# rx_path.net
KiCad netlist of a schematic drawn in Altium Designer
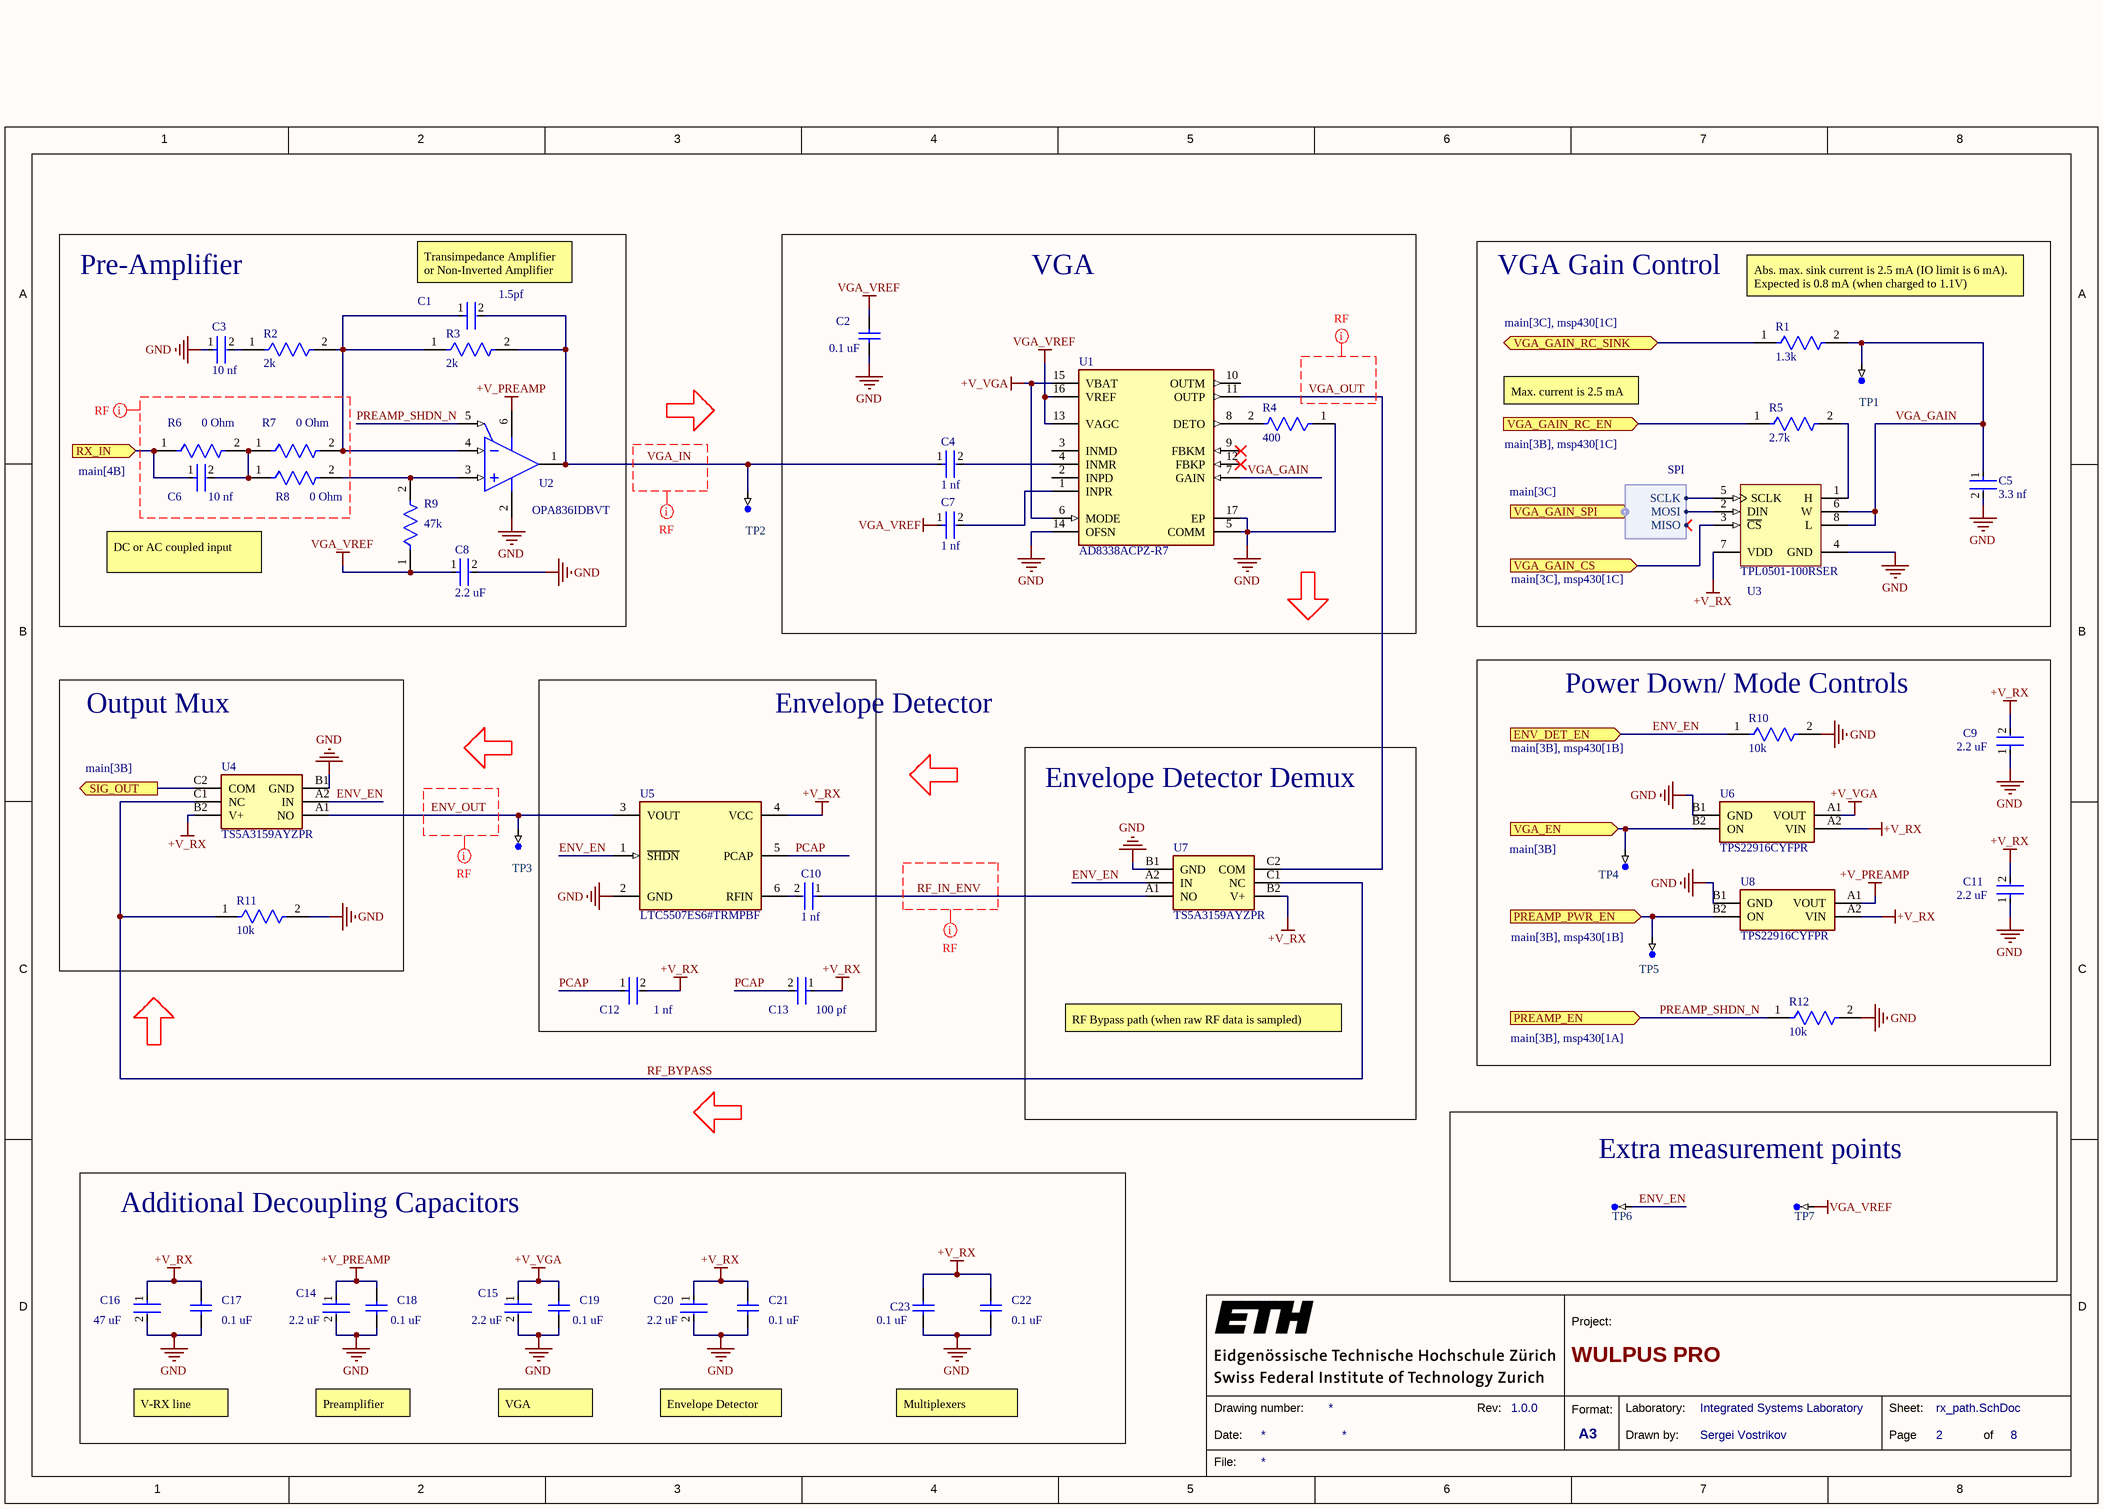
[diagram p0: rx_path.SchDoc]

(export (version "E")
  (design (tool "Eeschema 10.0.6"))
  (components
    (comp (ref "C1")
      (value "1.5pf")
      (footprint "FP-GJM155-0_05-IPC_C")
      (description "GJM1555C1H1R5BB01D")
      (fields (field (name "VOLTAGE") "50V"))
      (libsource (lib "Altium Content Vault") (part "02cd4be3c70576c341d710602a673aa"))
    )
    (comp (ref "C2")
      (value "0.1 uF")
      (footprint "CAPC1005X55X30LL05T10")
      (description "C0402C104K4RACTU")
      (fields (field (name "MANUFACTURER") "Kemet"))
      (libsource (lib "Altium Content Vault") (part "CAP"))
    )
    (comp (ref "C3")
      (value "10 nf")
      (footprint "FP-GRM033-0_03-IPC_B")
      (description "GRM033R71A103KA01D")
      (fields (field (name "VOLTAGE") "10V") (field (name "TOLERANCE") "10%"))
      (libsource (lib "Altium Content Vault") (part "b4654b650e69147ec39a6b967a45e02"))
    )
    (comp (ref "C4")
      (value "1 nf")
      (footprint "FP-GRM155-0_05-IPC_B")
      (description "GRM1555C1H102JA01D")
      (fields (field (name "TOLERANCE") "5%") (field (name "VOLTAGE") "50V"))
      (libsource (lib "Altium Content Vault") (part "02cd4be3c70576c341d710602a673aa"))
    )
    (comp (ref "C5")
      (value "3.3 nf")
      (footprint "FP-0402-L_1_0_1-W_0_5_0_1-IPC_C")
      (description "04025C332JAT2A")
      (fields (field (name "TOLERANCE") "5%"))
      (libsource (lib "Altium Content Vault") (part "b4654b650e69147ec39a6b967a45e02"))
    )
    (comp (ref "C6")
      (value "10 nf")
      (footprint "FP-GRM033-0_03-IPC_B")
      (description "GRM033R71A103KA01D")
      (fields (field (name "VOLTAGE") "10V") (field (name "TOLERANCE") "10%"))
      (libsource (lib "Altium Content Vault") (part "b4654b650e69147ec39a6b967a45e02"))
    )
    (comp (ref "C7")
      (value "1 nf")
      (footprint "FP-GRM155-0_05-IPC_B")
      (description "GRM1555C1H102JA01D")
      (fields (field (name "TOLERANCE") "5%") (field (name "VOLTAGE") "50V"))
      (libsource (lib "Altium Content Vault") (part "02cd4be3c70576c341d710602a673aa"))
    )
    (comp (ref "C8")
      (value "2.2 uF")
      (footprint "FP-C1005-050-0_15-0_1-MFG")
      (description "C1005X7S1A225K050BC")
      (fields (field (name "TOLERANCE") "10%"))
      (libsource (lib "Altium Content Vault") (part "b4654b650e69147ec39a6b967a45e02"))
    )
    (comp (ref "C9")
      (value "2.2 uF")
      (footprint "FP-C1005-050-0_15-0_1-MFG")
      (description "C1005X7S1A225K050BC")
      (fields (field (name "TOLERANCE") "10%"))
      (libsource (lib "Altium Content Vault") (part "b4654b650e69147ec39a6b967a45e02"))
    )
    (comp (ref "C10")
      (value "1 nf")
      (footprint "FP-GRM155-0_05-IPC_B")
      (description "GRM1555C1H102JA01D")
      (fields (field (name "TOLERANCE") "5%") (field (name "VOLTAGE") "50V"))
      (libsource (lib "Altium Content Vault") (part "02cd4be3c70576c341d710602a673aa"))
    )
    (comp (ref "C11")
      (value "2.2 uF")
      (footprint "FP-C1005-050-0_15-0_1-MFG")
      (description "C1005X7S1A225K050BC")
      (fields (field (name "TOLERANCE") "10%"))
      (libsource (lib "Altium Content Vault") (part "b4654b650e69147ec39a6b967a45e02"))
    )
    (comp (ref "C12")
      (value "1 nf")
      (footprint "FP-GRM155-0_05-IPC_B")
      (description "GRM1555C1H102JA01D")
      (fields (field (name "TOLERANCE") "5%") (field (name "VOLTAGE") "50V"))
      (libsource (lib "Altium Content Vault") (part "02cd4be3c70576c341d710602a673aa"))
    )
    (comp (ref "C13")
      (value "100 pf")
      (footprint "FP-0402-L_1_0_1-W_0_5_0_1-MFG")
      (description "04025A101FAT2A")
      (fields (field (name "VOLTAGE") "50V") (field (name "TOLERANCE") "1%"))
      (libsource (lib "Altium Content Vault") (part "b4654b650e69147ec39a6b967a45e02"))
    )
    (comp (ref "C14")
      (value "2.2 uF")
      (footprint "FP-C1005-050-0_15-0_1-MFG")
      (description "C1005X7S1A225K050BC")
      (fields (field (name "TOLERANCE") "10%"))
      (libsource (lib "Altium Content Vault") (part "b4654b650e69147ec39a6b967a45e02"))
    )
    (comp (ref "C15")
      (value "2.2 uF")
      (footprint "FP-C1005-050-0_15-0_1-MFG")
      (description "C1005X7S1A225K050BC")
      (fields (field (name "TOLERANCE") "10%"))
      (libsource (lib "Altium Content Vault") (part "b4654b650e69147ec39a6b967a45e02"))
    )
    (comp (ref "C16")
      (value "47 uF")
      (footprint "FP-GRM188-0_2-MFG")
      (description "GRM188R60J476ME01D")
      (fields (field (name "TOLERANCE") "20%"))
      (libsource (lib "Altium Content Vault") (part "b4654b650e69147ec39a6b967a45e02"))
    )
    (comp (ref "C17")
      (value "0.1 uF")
      (footprint "CAPC1005X55X30LL05T10")
      (description "C0402C104K4RACTU")
      (fields (field (name "MANUFACTURER") "Kemet"))
      (libsource (lib "Altium Content Vault") (part "CAP"))
    )
    (comp (ref "C18")
      (value "0.1 uF")
      (footprint "CAPC1005X55X30LL05T10")
      (description "C0402C104K4RACTU")
      (fields (field (name "MANUFACTURER") "Kemet"))
      (libsource (lib "Altium Content Vault") (part "CAP"))
    )
    (comp (ref "C19")
      (value "0.1 uF")
      (footprint "CAPC1005X55X30LL05T10")
      (description "C0402C104K4RACTU")
      (fields (field (name "MANUFACTURER") "Kemet"))
      (libsource (lib "Altium Content Vault") (part "CAP"))
    )
    (comp (ref "C20")
      (value "2.2 uF")
      (footprint "FP-C1005-050-0_15-0_1-MFG")
      (description "C1005X7S1A225K050BC")
      (fields (field (name "TOLERANCE") "10%"))
      (libsource (lib "Altium Content Vault") (part "b4654b650e69147ec39a6b967a45e02"))
    )
    (comp (ref "C21")
      (value "0.1 uF")
      (footprint "CAPC1005X55X30LL05T10")
      (description "C0402C104K4RACTU")
      (fields (field (name "MANUFACTURER") "Kemet"))
      (libsource (lib "Altium Content Vault") (part "CAP"))
    )
    (comp (ref "C22")
      (value "0.1 uF")
      (footprint "CAPC1005X55X30LL05T10")
      (description "C0402C104K4RACTU")
      (fields (field (name "MANUFACTURER") "Kemet"))
      (libsource (lib "Altium Content Vault") (part "CAP"))
    )
    (comp (ref "C23")
      (value "0.1 uF")
      (footprint "CAPC1005X55X30LL05T10")
      (description "C0402C104K4RACTU")
      (fields (field (name "MANUFACTURER") "Kemet"))
      (libsource (lib "Altium Content Vault") (part "CAP"))
    )
    (comp (ref "R1")
      (value "1.3k")
      (footprint "FP-CRCW0402-e3-IPC_B")
      (description "CRCW04021K30JNED")
      (fields (field (name "TOLERANCE") "5%"))
      (libsource (lib "Altium Content Vault") (part "1029c3af85768c4190bb7ad29bc67b5"))
    )
    (comp (ref "R2")
      (value "2k")
      (footprint "FP-ERJ2RK-MFG")
      (description "ERJ-2RKF2001X")
      (fields (field (name "TOLERANCE") "1%"))
      (libsource (lib "Altium Content Vault") (part "1029c3af85768c4190bb7ad29bc67b5"))
    )
    (comp (ref "R3")
      (value "2k")
      (footprint "FP-ERJ2RK-MFG")
      (description "ERJ-2RKF2001X")
      (fields (field (name "TOLERANCE") "1%"))
      (libsource (lib "Altium Content Vault") (part "1029c3af85768c4190bb7ad29bc67b5"))
    )
    (comp (ref "R4")
      (value "400")
      (footprint "FP-CRCW0402-C-e3-MFG")
      (description "CRCW04021R00FKEDC")
      (fields (field (name "TOLERANCE") "1%"))
      (libsource (lib "Altium Content Vault") (part "1029c3af85768c4190bb7ad29bc67b5"))
    )
    (comp (ref "R5")
      (value "2.7k")
      (footprint "FP-MCS0402-IPC_B")
      (description "MCS04020C2701FE000")
      (fields (field (name "TOLERANCE") "1%"))
      (libsource (lib "Altium Content Vault") (part "1029c3af85768c4190bb7ad29bc67b5"))
    )
    (comp (ref "R6")
      (value "0 Ohm")
      (footprint "FP-CRCW0402-e3-IPC_C")
      (description "CRCW04020000Z0ED")
      (fields (field (name "TOLERANCE") "5%"))
      (libsource (lib "Altium Content Vault") (part "1029c3af85768c4190bb7ad29bc67b5"))
    )
    (comp (ref "R7")
      (value "0 Ohm")
      (footprint "FP-CRCW0402-e3-IPC_C")
      (description "CRCW04020000Z0ED")
      (fields (field (name "TOLERANCE") "5%"))
      (libsource (lib "Altium Content Vault") (part "1029c3af85768c4190bb7ad29bc67b5"))
    )
    (comp (ref "R8")
      (value "0 Ohm")
      (footprint "FP-CRCW0402-e3-IPC_C")
      (description "CRCW04020000Z0ED")
      (fields (field (name "TOLERANCE") "5%"))
      (libsource (lib "Altium Content Vault") (part "1029c3af85768c4190bb7ad29bc67b5"))
    )
    (comp (ref "R9")
      (value "47k")
      (footprint "FP-RMCF0201-MFG")
      (description "RMCF0201JT47K0")
      (fields (field (name "TOLERANCE") "5%"))
      (libsource (lib "Altium Content Vault") (part "1029c3af85768c4190bb7ad29bc67b5"))
    )
    (comp (ref "R10")
      (value "10k")
      (footprint "FP-CRCW0402-e3-IPC_B")
      (description "CRCW040210K0JNED")
      (fields (field (name "TOLERANCE") "5%"))
      (libsource (lib "Altium Content Vault") (part "1029c3af85768c4190bb7ad29bc67b5"))
    )
    (comp (ref "R11")
      (value "10k")
      (footprint "FP-CRCW0402-e3-IPC_B")
      (description "CRCW040210K0JNED")
      (fields (field (name "TOLERANCE") "5%"))
      (libsource (lib "Altium Content Vault") (part "1029c3af85768c4190bb7ad29bc67b5"))
    )
    (comp (ref "R12")
      (value "10k")
      (footprint "FP-CRCW0402-e3-IPC_B")
      (description "CRCW040210K0JNED")
      (fields (field (name "TOLERANCE") "5%"))
      (libsource (lib "Altium Content Vault") (part "1029c3af85768c4190bb7ad29bc67b5"))
    )
    (comp (ref "TP1")
      (value "TP-SM-C-100")
      (footprint "TP-SM-C-100")
      (description "Test Point, Surface Mount, Circular, Pad Diameter 1 mm")
      (libsource (lib "wulpus") (part "CMP-0484-00002-1"))
    )
    (comp (ref "TP2")
      (value "TP-SM-C-100")
      (footprint "TP-SM-C-100")
      (description "Test Point, Surface Mount, Circular, Pad Diameter 1 mm")
      (libsource (lib "wulpus") (part "CMP-0484-00002-1"))
    )
    (comp (ref "TP3")
      (value "TP-SM-C-100")
      (footprint "TP-SM-C-100")
      (description "Test Point, Surface Mount, Circular, Pad Diameter 1 mm")
      (libsource (lib "wulpus") (part "CMP-0484-00002-1"))
    )
    (comp (ref "TP4")
      (value "TP-SM-C-100")
      (footprint "TP-SM-C-100")
      (description "Test Point, Surface Mount, Circular, Pad Diameter 1 mm")
      (libsource (lib "wulpus") (part "CMP-0484-00002-1"))
    )
    (comp (ref "TP5")
      (value "TP-SM-C-100")
      (footprint "TP-SM-C-100")
      (description "Test Point, Surface Mount, Circular, Pad Diameter 1 mm")
      (libsource (lib "wulpus") (part "CMP-0484-00002-1"))
    )
    (comp (ref "TP6")
      (value "TP-SM-C-100")
      (footprint "TP-SM-C-100")
      (description "Test Point, Surface Mount, Circular, Pad Diameter 1 mm")
      (libsource (lib "wulpus") (part "CMP-0484-00002-1"))
    )
    (comp (ref "TP7")
      (value "TP-SM-C-100")
      (footprint "TP-SM-C-100")
      (description "Test Point, Surface Mount, Circular, Pad Diameter 1 mm")
      (libsource (lib "wulpus") (part "CMP-0484-00002-1"))
    )
    (comp (ref "U1")
      (value "AD8338ACPZ-R7")
      (footprint "FP-CP-16-22-IPC_C")
      (description "IC OPAMP VGA 1 CIRCUIT 16LFCSP")
      (fields
        (field (name "OCTOPART") "https://octopart.com/ad8338acpz-r7-analog+devices-21054770")
        (field (name "MANUFACTURER") "Analog Devices")
      )
      (libsource (lib "Altium Content Vault") (part "4ce7887af0b7713ffabab50ab6d8fb3"))
    )
    (comp (ref "U2")
      (value "OPA836IDBVT")
      (footprint "DBV0006A_L")
      (fields (field (name "MANUFACTURER") "Texas Instruments"))
      (libsource (lib "wulpus") (part "CMP-0018-00480-2"))
    )
    (comp (ref "U3")
      (value "TPL0501-100RSER")
      (footprint "TI-RSE8_V")
      (fields (field (name "MANUFACTURER") "Texas Instruments"))
      (libsource (lib "Altium Content Vault") (part "TI-TPL0501-100RSE8"))
    )
    (comp (ref "U4")
      (value "TS5A3159AYZPR")
      (footprint "BGA6C50P2X3_89X139X50")
      (description "Analogue Switch ICs SPDT ANALOG SWITCH")
      (libsource (lib "") (part "TS5A3159AYZPR_1"))
    )
    (comp (ref "U5")
      (value "LTC5507ES6#TRMPBF")
      (footprint "FP-LTC5507ES6#TRMPBF-IPC_B")
      (description "IC RF DETECT 100KHZ-1GHZ TSOT23")
      (fields
        (field (name "OCTOPART") "https://octopart.com/ltc5507es6%23trmpbf-analog+devices-88320008")
        (field (name "MANUFACTURER") "Analog Devices")
      )
      (libsource (lib "Altium Content Vault") (part "942e158bd38935f4e9b1d9ad82e87f8"))
    )
    (comp (ref "U6")
      (value "TPS22916CYFPR")
      (footprint "BGA4C40P2X2_78X78X50")
      (description "TPS22916 5.5-V, 2-A Ultra-Low Leakage Load Switch")
      (libsource (lib "TPS22916CYFPR") (part "TPS22916CYFPR"))
    )
    (comp (ref "U7")
      (value "TS5A3159AYZPR")
      (footprint "BGA6C50P2X3_89X139X50")
      (description "Analogue Switch ICs SPDT ANALOG SWITCH")
      (libsource (lib "TS5A3159AYZPR") (part "TS5A3159AYZPR"))
    )
    (comp (ref "U8")
      (value "TPS22916CYFPR")
      (footprint "BGA4C40P2X2_78X78X50")
      (description "TPS22916 5.5-V, 2-A Ultra-Low Leakage Load Switch")
      (libsource (lib "TPS22916CYFPR") (part "TPS22916CYFPR"))
    )
  )
  (nets
    (net (code "2") (name "+V_PREAMP") (class "Default")
      (node (ref "C14") (pin "1") (pinfunction "1_1") (pintype "passive"))
      (node (ref "C18") (pin "2") (pinfunction "2_2") (pintype "passive"))
      (node (ref "U2") (pin "6") (pinfunction "VS+_6") (pintype "power_in"))
      (node (ref "U8") (pin "A1") (pinfunction "VOUT_A1") (pintype "passive"))
    )
    (net (code "3") (name "+V_RX") (class "Default")
      (node (ref "C11") (pin "2") (pinfunction "2_2") (pintype "passive"))
      (node (ref "C12") (pin "2") (pinfunction "2_2") (pintype "passive"))
      (node (ref "C13") (pin "1") (pinfunction "1_1") (pintype "passive"))
      (node (ref "C16") (pin "1") (pinfunction "1_1") (pintype "passive"))
      (node (ref "C17") (pin "2") (pinfunction "2_2") (pintype "passive"))
      (node (ref "C20") (pin "1") (pinfunction "1_1") (pintype "passive"))
      (node (ref "C21") (pin "2") (pinfunction "2_2") (pintype "passive"))
      (node (ref "C22") (pin "2") (pinfunction "2_2") (pintype "passive"))
      (node (ref "C23") (pin "2") (pinfunction "2_2") (pintype "passive"))
      (node (ref "C9") (pin "2") (pinfunction "2_2") (pintype "passive"))
      (node (ref "U3") (pin "7") (pinfunction "VDD_7") (pintype "power_in"))
      (node (ref "U4") (pin "B2") (pinfunction "V+_B2") (pintype "passive"))
      (node (ref "U5") (pin "4") (pinfunction "VCC_4") (pintype "power_in"))
      (node (ref "U6") (pin "A2") (pinfunction "VIN_A2") (pintype "passive"))
      (node (ref "U7") (pin "B2") (pinfunction "V+_B2") (pintype "passive"))
      (node (ref "U8") (pin "A2") (pinfunction "VIN_A2") (pintype "passive"))
    )
    (net (code "4") (name "+V_VGA") (class "Default")
      (node (ref "C15") (pin "1") (pinfunction "1_1") (pintype "passive"))
      (node (ref "C19") (pin "2") (pinfunction "2_2") (pintype "passive"))
      (node (ref "U1") (pin "15") (pinfunction "VBAT_15") (pintype "power_in"))
      (node (ref "U1") (pin "6") (pinfunction "MODE_6") (pintype "input"))
      (node (ref "U6") (pin "A1") (pinfunction "VOUT_A1") (pintype "passive"))
    )
    (net (code "5") (name "/ENV_EN") (class "Default")
      (node (ref "R10") (pin "1") (pinfunction "1_1") (pintype "passive"))
      (node (ref "TP6") (pin "1") (pinfunction "1_1") (pintype "input"))
      (node (ref "U4") (pin "A2") (pinfunction "IN_A2") (pintype "passive"))
      (node (ref "U5") (pin "1") (pinfunction "~{SHDN}_1") (pintype "input"))
      (node (ref "U7") (pin "A2") (pinfunction "IN_A2") (pintype "passive"))
    )
    (net (code "6") (name "/ENV_OUT") (class "Default")
      (node (ref "TP3") (pin "1") (pinfunction "1_1") (pintype "input"))
      (node (ref "U4") (pin "A1") (pinfunction "NO_A1") (pintype "passive"))
      (node (ref "U5") (pin "3") (pinfunction "VOUT_3") (pintype "passive"))
    )
    (net (code "7") (name "/MOSI") (class "Default")
      (node (ref "U3") (pin "2") (pinfunction "DIN_2") (pintype "input"))
    )
    (net (code "8") (name "/PCAP") (class "Default")
      (node (ref "C12") (pin "1") (pinfunction "1_1") (pintype "passive"))
      (node (ref "C13") (pin "2") (pinfunction "2_2") (pintype "passive"))
      (node (ref "U5") (pin "5") (pinfunction "PCAP_5") (pintype "passive"))
    )
    (net (code "9") (name "/PREAMP_PWR_EN") (class "Default")
      (node (ref "TP5") (pin "1") (pinfunction "1_1") (pintype "input"))
      (node (ref "U8") (pin "B2") (pinfunction "ON_B2") (pintype "passive"))
    )
    (net (code "10") (name "/PREAMP_SHDN_N") (class "Default")
      (node (ref "R12") (pin "1") (pinfunction "1_1") (pintype "passive"))
      (node (ref "U2") (pin "5") (pinfunction "~{PD}_5") (pintype "input"))
    )
    (net (code "11") (name "/RF_BYPASS") (class "Default")
      (node (ref "R11") (pin "1") (pinfunction "1_1") (pintype "passive"))
      (node (ref "U4") (pin "C1") (pinfunction "NC_C1") (pintype "passive"))
      (node (ref "U7") (pin "C1") (pinfunction "NC_C1") (pintype "passive"))
    )
    (net (code "12") (name "/RF_IN_ENV") (class "Default")
      (node (ref "C10") (pin "1") (pinfunction "1_1") (pintype "passive"))
      (node (ref "U7") (pin "A1") (pinfunction "NO_A1") (pintype "passive"))
    )
    (net (code "13") (name "/RX_IN") (class "Default")
      (node (ref "C6") (pin "1") (pinfunction "1_1") (pintype "passive"))
      (node (ref "R6") (pin "1") (pinfunction "1_1") (pintype "passive"))
    )
    (net (code "14") (name "/SCLK") (class "Default")
      (node (ref "U3") (pin "5") (pinfunction "SCLK_5") (pintype "input"))
    )
    (net (code "15") (name "/SIG_OUT") (class "Default")
      (node (ref "U4") (pin "C2") (pinfunction "COM_C2") (pintype "passive"))
    )
    (net (code "16") (name "/VGA_EN") (class "Default")
      (node (ref "TP4") (pin "1") (pinfunction "1_1") (pintype "input"))
      (node (ref "U6") (pin "B2") (pinfunction "ON_B2") (pintype "passive"))
    )
    (net (code "17") (name "/VGA_GAIN") (class "Default")
      (node (ref "C5") (pin "1") (pinfunction "1_1") (pintype "passive"))
      (node (ref "R1") (pin "2") (pinfunction "2_2") (pintype "passive"))
      (node (ref "TP1") (pin "1") (pinfunction "1_1") (pintype "input"))
      (node (ref "U1") (pin "7") (pinfunction "GAIN_7") (pintype "input"))
      (node (ref "U3") (pin "6") (pinfunction "W_6") (pintype "passive"))
      (node (ref "U3") (pin "8") (pinfunction "L_8") (pintype "passive"))
    )
    (net (code "18") (name "/VGA_GAIN_CS") (class "Default")
      (node (ref "U3") (pin "3") (pinfunction "~{CS}_3") (pintype "input"))
    )
    (net (code "19") (name "/VGA_GAIN_RC_EN") (class "Default")
      (node (ref "R5") (pin "1") (pinfunction "1_1") (pintype "passive"))
    )
    (net (code "20") (name "/VGA_GAIN_RC_SINK") (class "Default")
      (node (ref "R1") (pin "1") (pinfunction "1_1") (pintype "passive"))
    )
    (net (code "21") (name "/VGA_IN") (class "Default")
      (node (ref "C1") (pin "2") (pinfunction "2_2") (pintype "passive"))
      (node (ref "C4") (pin "1") (pinfunction "1_1") (pintype "passive"))
      (node (ref "R3") (pin "2") (pinfunction "2_2") (pintype "passive"))
      (node (ref "TP2") (pin "1") (pinfunction "1_1") (pintype "input"))
      (node (ref "U2") (pin "1") (pinfunction "VOUT_1") (pintype "tri_state"))
    )
    (net (code "22") (name "/VGA_OUT") (class "Default")
      (node (ref "U1") (pin "11") (pinfunction "OUTP_11") (pintype "output"))
      (node (ref "U7") (pin "C2") (pinfunction "COM_C2") (pintype "passive"))
    )
    (net (code "24") (name "GND") (class "Default")
      (node (ref "C11") (pin "1") (pinfunction "1_1") (pintype "passive"))
      (node (ref "C14") (pin "2") (pinfunction "2_2") (pintype "passive"))
      (node (ref "C15") (pin "2") (pinfunction "2_2") (pintype "passive"))
      (node (ref "C16") (pin "2") (pinfunction "2_2") (pintype "passive"))
      (node (ref "C17") (pin "1") (pinfunction "1_1") (pintype "passive"))
      (node (ref "C18") (pin "1") (pinfunction "1_1") (pintype "passive"))
      (node (ref "C19") (pin "1") (pinfunction "1_1") (pintype "passive"))
      (node (ref "C2") (pin "1") (pinfunction "1_1") (pintype "passive"))
      (node (ref "C20") (pin "2") (pinfunction "2_2") (pintype "passive"))
      (node (ref "C21") (pin "1") (pinfunction "1_1") (pintype "passive"))
      (node (ref "C22") (pin "1") (pinfunction "1_1") (pintype "passive"))
      (node (ref "C23") (pin "1") (pinfunction "1_1") (pintype "passive"))
      (node (ref "C3") (pin "1") (pinfunction "1_1") (pintype "passive"))
      (node (ref "C5") (pin "2") (pinfunction "2_2") (pintype "passive"))
      (node (ref "C8") (pin "2") (pinfunction "2_2") (pintype "passive"))
      (node (ref "C9") (pin "1") (pinfunction "1_1") (pintype "passive"))
      (node (ref "R10") (pin "2") (pinfunction "2_2") (pintype "passive"))
      (node (ref "R11") (pin "2") (pinfunction "2_2") (pintype "passive"))
      (node (ref "R12") (pin "2") (pinfunction "2_2") (pintype "passive"))
      (node (ref "R4") (pin "1") (pinfunction "1_1") (pintype "passive"))
      (node (ref "U1") (pin "14") (pinfunction "OFSN_14") (pintype "passive"))
      (node (ref "U1") (pin "17") (pinfunction "EP_17") (pintype "power_in"))
      (node (ref "U1") (pin "5") (pinfunction "COMM_5") (pintype "power_in"))
      (node (ref "U2") (pin "2") (pinfunction "VS-_2") (pintype "power_in"))
      (node (ref "U3") (pin "4") (pinfunction "GND_4") (pintype "power_in"))
      (node (ref "U4") (pin "B1") (pinfunction "GND_B1") (pintype "passive"))
      (node (ref "U5") (pin "2") (pinfunction "GND_2") (pintype "power_in"))
      (node (ref "U6") (pin "B1") (pinfunction "GND_B1") (pintype "passive"))
      (node (ref "U7") (pin "B1") (pinfunction "GND_B1") (pintype "passive"))
      (node (ref "U8") (pin "B1") (pinfunction "GND_B1") (pintype "passive"))
    )
    (net (code "25") (name "Net-(C3-Pad2)") (class "Default")
      (node (ref "C3") (pin "2") (pinfunction "2_2") (pintype "passive"))
      (node (ref "R2") (pin "1") (pinfunction "1_1") (pintype "passive"))
    )
    (net (code "26") (name "Net-(C6-Pad2)") (class "Default")
      (node (ref "C6") (pin "2") (pinfunction "2_2") (pintype "passive"))
      (node (ref "R6") (pin "2") (pinfunction "2_2") (pintype "passive"))
      (node (ref "R7") (pin "1") (pinfunction "1_1") (pintype "passive"))
      (node (ref "R8") (pin "1") (pinfunction "1_1") (pintype "passive"))
    )
    (net (code "27") (name "Net-(U1-DETO)") (class "Default")
      (node (ref "R4") (pin "2") (pinfunction "2_2") (pintype "passive"))
      (node (ref "U1") (pin "8") (pinfunction "DETO_8") (pintype "output"))
    )
    (net (code "28") (name "Net-(U1-INMR)") (class "Default")
      (node (ref "C4") (pin "2") (pinfunction "2_2") (pintype "passive"))
      (node (ref "U1") (pin "4") (pinfunction "INMR_4") (pintype "passive"))
    )
    (net (code "29") (name "Net-(U1-INPR)") (class "Default")
      (node (ref "C7") (pin "2") (pinfunction "2_2") (pintype "passive"))
      (node (ref "U1") (pin "1") (pinfunction "INPR_1") (pintype "passive"))
    )
    (net (code "30") (name "Net-(U2-VIN+)") (class "Default")
      (node (ref "R8") (pin "2") (pinfunction "2_2") (pintype "passive"))
      (node (ref "R9") (pin "2") (pinfunction "2_2") (pintype "passive"))
      (node (ref "U2") (pin "3") (pinfunction "VIN+_3") (pintype "input"))
    )
    (net (code "31") (name "Net-(U2-VIN-)") (class "Default")
      (node (ref "C1") (pin "1") (pinfunction "1_1") (pintype "passive"))
      (node (ref "R2") (pin "2") (pinfunction "2_2") (pintype "passive"))
      (node (ref "R3") (pin "1") (pinfunction "1_1") (pintype "passive"))
      (node (ref "R7") (pin "2") (pinfunction "2_2") (pintype "passive"))
      (node (ref "U2") (pin "4") (pinfunction "VIN-_4") (pintype "input"))
    )
    (net (code "32") (name "Net-(U3-H)") (class "Default")
      (node (ref "R5") (pin "2") (pinfunction "2_2") (pintype "passive"))
      (node (ref "U3") (pin "1") (pinfunction "H_1") (pintype "passive"))
    )
    (net (code "33") (name "Net-(U5-RFIN)") (class "Default")
      (node (ref "C10") (pin "2") (pinfunction "2_2") (pintype "passive"))
      (node (ref "U5") (pin "6") (pinfunction "RFIN_6") (pintype "passive"))
    )
    (net (code "34") (name "VGA_VREF") (class "Default")
      (node (ref "C2") (pin "2") (pinfunction "2_2") (pintype "passive"))
      (node (ref "C7") (pin "1") (pinfunction "1_1") (pintype "passive"))
      (node (ref "C8") (pin "1") (pinfunction "1_1") (pintype "passive"))
      (node (ref "R9") (pin "1") (pinfunction "1_1") (pintype "passive"))
      (node (ref "TP7") (pin "1") (pinfunction "1_1") (pintype "input"))
      (node (ref "U1") (pin "13") (pinfunction "VAGC_13") (pintype "power_in"))
      (node (ref "U1") (pin "16") (pinfunction "VREF_16") (pintype "power_in"))
    )
    (net (code "35") (name "unconnected-(U1-FBKM-Pad9)") (class "Default")
      (node (ref "U1") (pin "9") (pinfunction "FBKM_9") (pintype "input+no_connect"))
    )
    (net (code "36") (name "unconnected-(U1-FBKP-Pad12)") (class "Default")
      (node (ref "U1") (pin "12") (pinfunction "FBKP_12") (pintype "input+no_connect"))
    )
    (net (code "37") (name "unconnected-(U1-INMD-Pad3)") (class "Default")
      (node (ref "U1") (pin "3") (pinfunction "INMD_3") (pintype "passive"))
    )
    (net (code "38") (name "unconnected-(U1-INPD-Pad2)") (class "Default")
      (node (ref "U1") (pin "2") (pinfunction "INPD_2") (pintype "passive"))
    )
    (net (code "39") (name "unconnected-(U1-OUTM-Pad10)") (class "Default")
      (node (ref "U1") (pin "10") (pinfunction "OUTM_10") (pintype "output"))
    )
  )
)
